# 20pin_2x10_1_27mm_to_2_54mm.net
KiCad netlist of a schematic drawn in Altium Designer
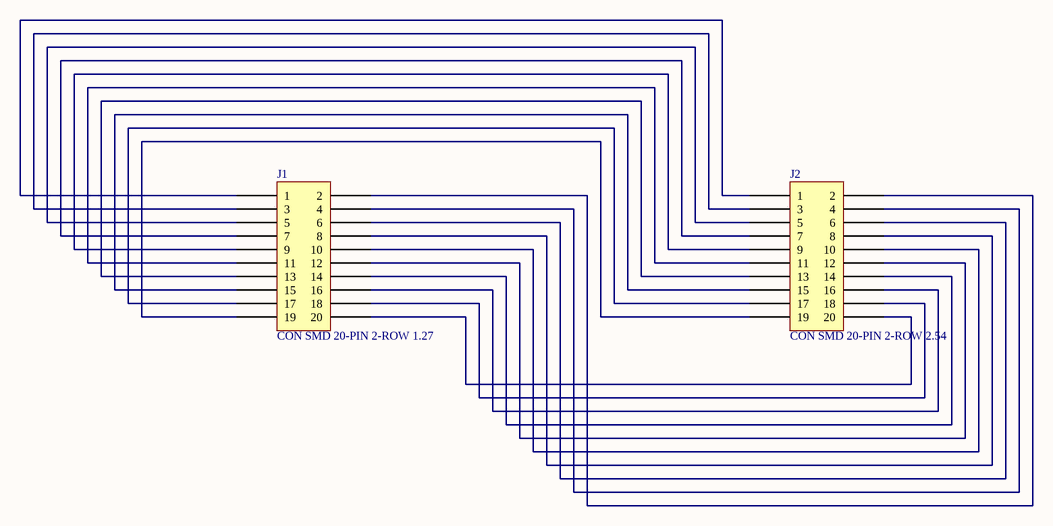
[diagram p0: 20pin_2x10_1.27mm_to_2.54mm.SchDoc]

(export (version "E")
  (design (tool "Eeschema 10.0.6"))
  (components
    (comp (ref "J1")
      (value "CON SMD 20-PIN 2-ROW 1.27")
      (footprint "SMD HEADER 2x10 1.27")
      (description "FTSH-110-01-L-DV")
      (libsource (lib "AD_Library") (part "CON SMD 20-PIN 2-ROW 1.27"))
    )
    (comp (ref "J2")
      (value "CON SMD 20-PIN 2-ROW 2.54")
      (footprint "SMD HEADER 2x10 2.54")
      (description "HTSS-110-01-L-DV")
      (libsource (lib "AD_Library") (part "CON SMD 20-PIN 2-ROW 2.54"))
    )
  )
  (nets
    (net (code "1") (name "Net-(J1-Pad1)") (class "Default")
      (node (ref "J1") (pin "1") (pinfunction "1_1") (pintype "passive"))
      (node (ref "J2") (pin "1") (pinfunction "1_1") (pintype "passive"))
    )
    (net (code "2") (name "Net-(J1-Pad2)") (class "Default")
      (node (ref "J1") (pin "2") (pinfunction "2_2") (pintype "passive"))
      (node (ref "J2") (pin "2") (pinfunction "2_2") (pintype "passive"))
    )
    (net (code "3") (name "Net-(J1-Pad3)") (class "Default")
      (node (ref "J1") (pin "3") (pinfunction "3_3") (pintype "passive"))
      (node (ref "J2") (pin "3") (pinfunction "3_3") (pintype "passive"))
    )
    (net (code "4") (name "Net-(J1-Pad4)") (class "Default")
      (node (ref "J1") (pin "4") (pinfunction "4_4") (pintype "passive"))
      (node (ref "J2") (pin "4") (pinfunction "4_4") (pintype "passive"))
    )
    (net (code "5") (name "Net-(J1-Pad5)") (class "Default")
      (node (ref "J1") (pin "5") (pinfunction "5_5") (pintype "passive"))
      (node (ref "J2") (pin "5") (pinfunction "5_5") (pintype "passive"))
    )
    (net (code "6") (name "Net-(J1-Pad6)") (class "Default")
      (node (ref "J1") (pin "6") (pinfunction "6_6") (pintype "passive"))
      (node (ref "J2") (pin "6") (pinfunction "6_6") (pintype "passive"))
    )
    (net (code "7") (name "Net-(J1-Pad7)") (class "Default")
      (node (ref "J1") (pin "7") (pinfunction "7_7") (pintype "passive"))
      (node (ref "J2") (pin "7") (pinfunction "7_7") (pintype "passive"))
    )
    (net (code "8") (name "Net-(J1-Pad8)") (class "Default")
      (node (ref "J1") (pin "8") (pinfunction "8_8") (pintype "passive"))
      (node (ref "J2") (pin "8") (pinfunction "8_8") (pintype "passive"))
    )
    (net (code "9") (name "Net-(J1-Pad9)") (class "Default")
      (node (ref "J1") (pin "9") (pinfunction "9_9") (pintype "passive"))
      (node (ref "J2") (pin "9") (pinfunction "9_9") (pintype "passive"))
    )
    (net (code "10") (name "Net-(J1-Pad10)") (class "Default")
      (node (ref "J1") (pin "10") (pinfunction "10_10") (pintype "passive"))
      (node (ref "J2") (pin "10") (pinfunction "10_10") (pintype "passive"))
    )
    (net (code "11") (name "Net-(J1-Pad11)") (class "Default")
      (node (ref "J1") (pin "11") (pinfunction "11_11") (pintype "passive"))
      (node (ref "J2") (pin "11") (pinfunction "11_11") (pintype "passive"))
    )
    (net (code "12") (name "Net-(J1-Pad12)") (class "Default")
      (node (ref "J1") (pin "12") (pinfunction "12_12") (pintype "passive"))
      (node (ref "J2") (pin "12") (pinfunction "12_12") (pintype "passive"))
    )
    (net (code "13") (name "Net-(J1-Pad13)") (class "Default")
      (node (ref "J1") (pin "13") (pinfunction "13_13") (pintype "passive"))
      (node (ref "J2") (pin "13") (pinfunction "13_13") (pintype "passive"))
    )
    (net (code "14") (name "Net-(J1-Pad14)") (class "Default")
      (node (ref "J1") (pin "14") (pinfunction "14_14") (pintype "passive"))
      (node (ref "J2") (pin "14") (pinfunction "14_14") (pintype "passive"))
    )
    (net (code "15") (name "Net-(J1-Pad15)") (class "Default")
      (node (ref "J1") (pin "15") (pinfunction "15_15") (pintype "passive"))
      (node (ref "J2") (pin "15") (pinfunction "15_15") (pintype "passive"))
    )
    (net (code "16") (name "Net-(J1-Pad16)") (class "Default")
      (node (ref "J1") (pin "16") (pinfunction "16_16") (pintype "passive"))
      (node (ref "J2") (pin "16") (pinfunction "16_16") (pintype "passive"))
    )
    (net (code "17") (name "Net-(J1-Pad17)") (class "Default")
      (node (ref "J1") (pin "17") (pinfunction "17_17") (pintype "passive"))
      (node (ref "J2") (pin "17") (pinfunction "17_17") (pintype "passive"))
    )
    (net (code "18") (name "Net-(J1-Pad18)") (class "Default")
      (node (ref "J1") (pin "18") (pinfunction "18_18") (pintype "passive"))
      (node (ref "J2") (pin "18") (pinfunction "18_18") (pintype "passive"))
    )
    (net (code "19") (name "Net-(J1-Pad19)") (class "Default")
      (node (ref "J1") (pin "19") (pinfunction "19_19") (pintype "passive"))
      (node (ref "J2") (pin "19") (pinfunction "19_19") (pintype "passive"))
    )
    (net (code "20") (name "Net-(J1-Pad20)") (class "Default")
      (node (ref "J1") (pin "20") (pinfunction "20_20") (pintype "passive"))
      (node (ref "J2") (pin "20") (pinfunction "20_20") (pintype "passive"))
    )
  )
)
